# Sensors.net
KiCad netlist of a schematic drawn in Altium Designer
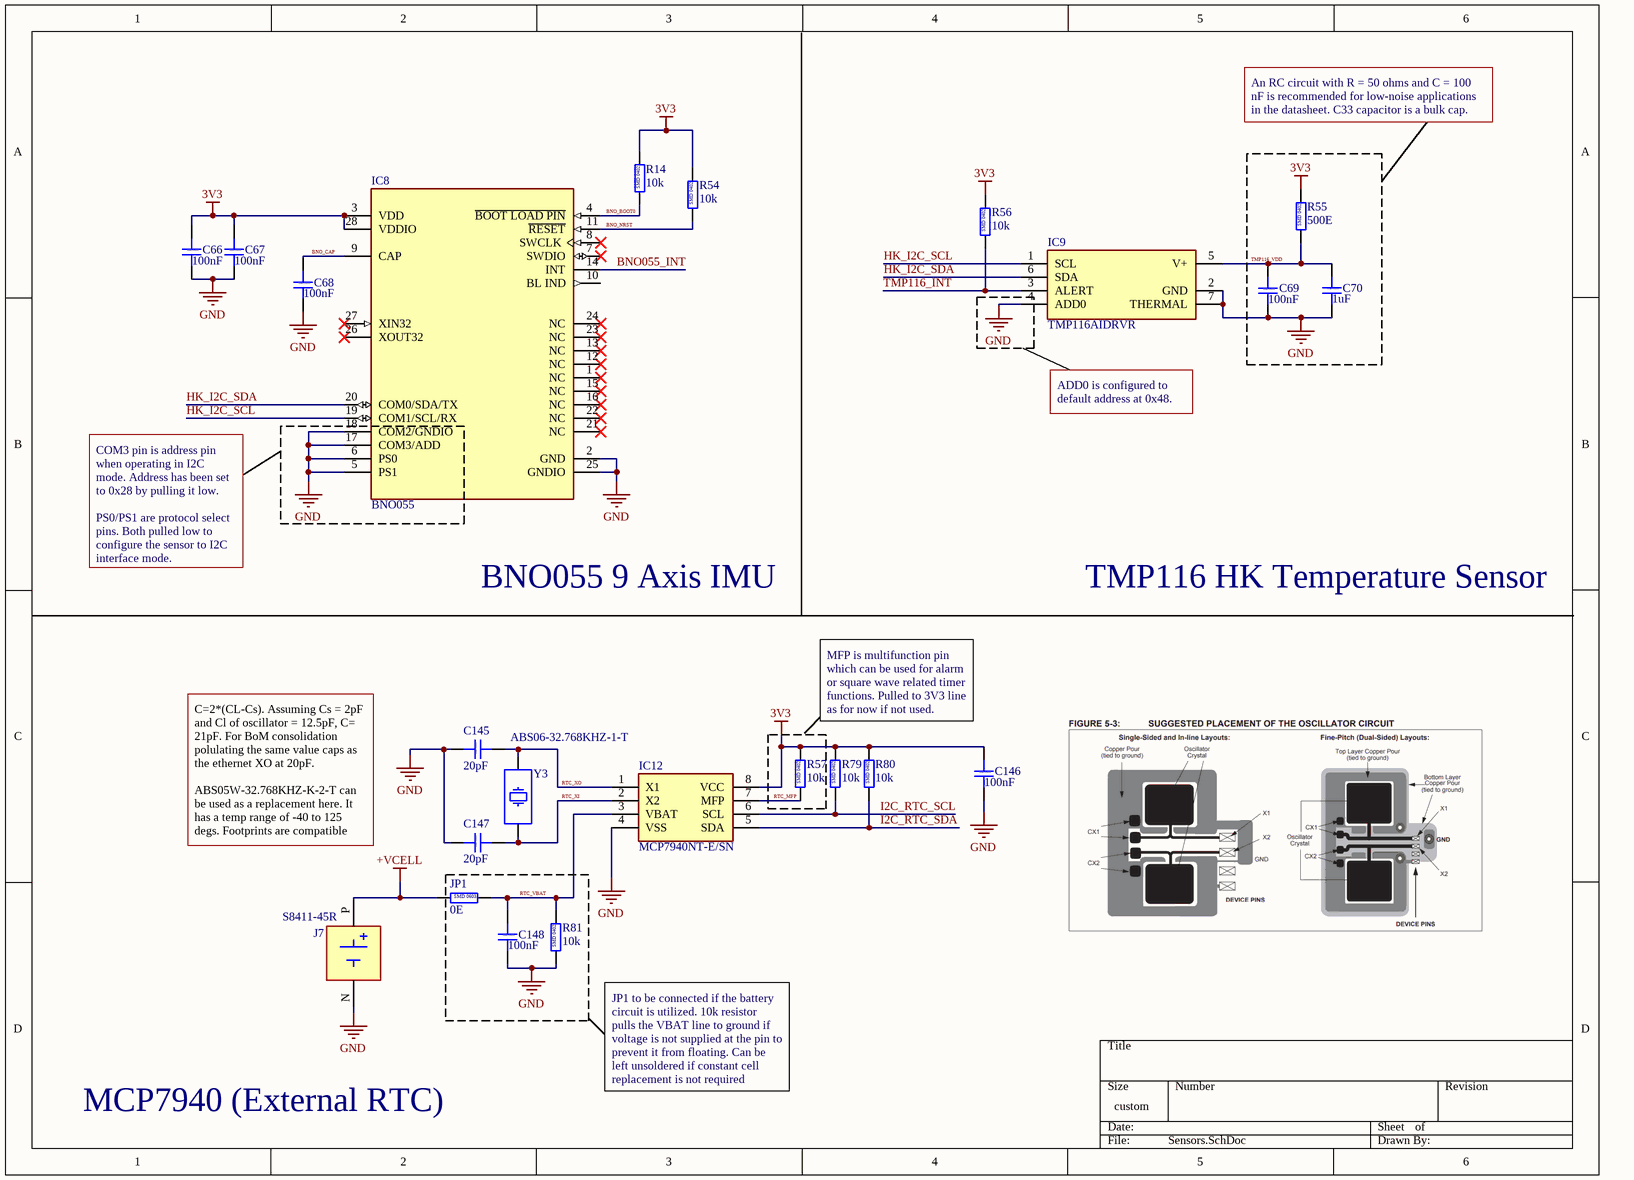
[diagram p0: Sensors.SchDoc]

(export (version "E")
  (design (tool "Eeschema 10.0.6"))
  (components
    (comp (ref "C66")
      (value "100nF")
      (footprint "CAP_0402")
      (description "Capacitor SMD 0402 RATED")
      (libsource (lib "STeRG-Passives-Standard") (part "Capacitor-SMD-0402"))
    )
    (comp (ref "C67")
      (value "100nF")
      (footprint "CAP_0402")
      (description "Capacitor SMD 0402 RATED")
      (libsource (lib "STeRG-Passives-Standard") (part "Capacitor-SMD-0402"))
    )
    (comp (ref "C68")
      (value "100nF")
      (footprint "CAP_0402")
      (description "Capacitor SMD 0402 RATED")
      (libsource (lib "STeRG-Passives-Standard") (part "Capacitor-SMD-0402"))
    )
    (comp (ref "C69")
      (value "100nF")
      (footprint "CAP_0402")
      (description "Capacitor SMD 0402 RATED")
      (libsource (lib "STeRG-Passives-Standard") (part "Capacitor-SMD-0402"))
    )
    (comp (ref "C70")
      (value "1uF")
      (footprint "CAP_0402")
      (description "Capacitor SMD 0402 RATED")
      (libsource (lib "STeRG-Passives-Standard") (part "Capacitor-SMD-0402"))
    )
    (comp (ref "C145")
      (value "20pF")
      (footprint "CAP_0402")
      (description "Capacitor SMD 0402 RATED")
      (libsource (lib "STeRG-Passives-Standard") (part "Capacitor-SMD-0402"))
    )
    (comp (ref "C146")
      (value "100nF")
      (footprint "CAP_0402")
      (description "Capacitor SMD 0402 RATED")
      (libsource (lib "STeRG-Passives-Standard") (part "Capacitor-SMD-0402"))
    )
    (comp (ref "C147")
      (value "20pF")
      (footprint "CAP_0402")
      (description "Capacitor SMD 0402 RATED")
      (libsource (lib "STeRG-Passives-Standard") (part "Capacitor-SMD-0402"))
    )
    (comp (ref "C148")
      (value "100nF")
      (footprint "CAP_0402")
      (description "Capacitor SMD 0402 RATED")
      (libsource (lib "STeRG-Passives-Standard") (part "Capacitor-SMD-0402"))
    )
    (comp (ref "IC8")
      (value "BNO055")
      (footprint "BNO0XX")
      (libsource (lib "STeRG-ICs-Standard") (part "BNO055"))
    )
    (comp (ref "IC9")
      (value "TMP116AIDRVR")
      (footprint "SON65P200X200X80-7N")
      (description "Integrated Circuit")
      (fields (field (name "MOUSER PART NUMBER") "595-TMP116AIDRVR"))
      (libsource (lib "STeRG-ICs-Standard") (part "TMP116AIDRVR"))
    )
    (comp (ref "IC12")
      (value "MCP7940NT-E/SN")
      (footprint "SamacSys:SOIC127P600X175-8N")
      (description "Integrated Circuit")
      (fields
        (field (name "MANUFACTURER_PART_NUMBER") "MCP7940NT-I/SN")
        (field (name "MOUSER PART NUMBER") "579-MCP7940NT-I/SN")
      )
      (libsource (lib "*") (part "MCP7940NT-I_SN"))
    )
    (comp (ref "J7")
      (value "S8411-45R")
      (footprint "HARWIN_S8411-45R")
      (description "Coin Cell Battery Retainer, Horizontal SMT, for CR1220 Coin Cell Batteries, Tape & Reeled")
      (fields (field (name "MF") "Harwin"))
      (libsource (lib "STeRG-Passives-Standard") (part "S8411-45R"))
    )
    (comp (ref "JP1")
      (value "0E")
      (footprint "RES_0603")
      (description "Resistor SMD 0603 RATED")
      (libsource (lib "STeRG-Passives-Standard") (part "Resistor-SMD-0603"))
    )
    (comp (ref "R14")
      (value "10k")
      (footprint "RES_0402")
      (description "Resistor SMD 0402 RATED")
      (libsource (lib "STeRG-Passives-Standard") (part "Resistor-SMD-0402"))
    )
    (comp (ref "R54")
      (value "10k")
      (footprint "RES_0402")
      (description "Resistor SMD 0402 RATED")
      (libsource (lib "STeRG-Passives-Standard") (part "Resistor-SMD-0402"))
    )
    (comp (ref "R55")
      (value "500E")
      (footprint "RES_0402")
      (description "Resistor SMD 0402 RATED")
      (libsource (lib "STeRG-Passives-Standard") (part "Resistor-SMD-0402"))
    )
    (comp (ref "R56")
      (value "10k")
      (footprint "RES_0402")
      (description "Resistor SMD 0402 RATED")
      (libsource (lib "STeRG-Passives-Standard") (part "Resistor-SMD-0402"))
    )
    (comp (ref "R57")
      (value "10k")
      (footprint "RES_0402")
      (description "Resistor SMD 0402 RATED")
      (libsource (lib "STeRG-Passives-Standard") (part "Resistor-SMD-0402"))
    )
    (comp (ref "R79")
      (value "10k")
      (footprint "RES_0402")
      (description "Resistor SMD 0402 RATED")
      (libsource (lib "STeRG-Passives-Standard") (part "Resistor-SMD-0402"))
    )
    (comp (ref "R80")
      (value "10k")
      (footprint "RES_0402")
      (description "Resistor SMD 0402 RATED")
      (libsource (lib "STeRG-Passives-Standard") (part "Resistor-SMD-0402"))
    )
    (comp (ref "R81")
      (value "10k")
      (footprint "RES_0402")
      (description "Resistor SMD 0402 RATED")
      (libsource (lib "STeRG-Passives-Standard") (part "Resistor-SMD-0402"))
    )
    (comp (ref "Y3")
      (value "ABS06-32.768KHZ-1-T")
      (footprint "SamacSys:ABS06")
      (description "Crystal or Oscillator")
      (fields (field (name "MOUSER PART NUMBER") "815-ABS06-32.7K-1-T"))
      (libsource (lib "STeRG-Passives-Standard") (part "ABS06-32.768KHZ-1-T"))
    )
  )
  (nets
    (net (code "1") (name "+VCELL") (class "Default")
      (node (ref "J7") (pin "P") (pinfunction "POS_P") (pintype "passive"))
      (node (ref "JP1") (pin "1") (pinfunction "1_1") (pintype "passive"))
    )
    (net (code "2") (name "/BNO055_INT") (class "Default")
      (node (ref "IC8") (pin "14") (pinfunction "INT_14") (pintype "passive"))
    )
    (net (code "3") (name "/BNO_BOOT0") (class "Default")
      (node (ref "IC8") (pin "4") (pinfunction "~{BOOT_LOAD_PIN}_4") (pintype "input"))
      (node (ref "R14") (pin "1") (pinfunction "1_1") (pintype "passive"))
    )
    (net (code "4") (name "/BNO_CAP") (class "Default")
      (node (ref "C68") (pin "1") (pinfunction "1_1") (pintype "passive"))
      (node (ref "IC8") (pin "9") (pinfunction "CAP_9") (pintype "passive"))
    )
    (net (code "5") (name "/BNO_NRST") (class "Default")
      (node (ref "IC8") (pin "11") (pinfunction "~{RESET}_11") (pintype "input"))
      (node (ref "R54") (pin "1") (pinfunction "1_1") (pintype "passive"))
    )
    (net (code "6") (name "/HK_I2C_SCL") (class "Default")
      (node (ref "IC8") (pin "19") (pinfunction "COM1/SCL/RX_19") (pintype "bidirectional"))
      (node (ref "IC9") (pin "1") (pinfunction "SCL_1") (pintype "passive"))
    )
    (net (code "7") (name "/HK_I2C_SDA") (class "Default")
      (node (ref "IC8") (pin "20") (pinfunction "COM0/SDA/TX_20") (pintype "bidirectional"))
      (node (ref "IC9") (pin "6") (pinfunction "SDA_6") (pintype "passive"))
    )
    (net (code "8") (name "/I2C_RTC_SCL") (class "Default")
      (node (ref "IC12") (pin "6") (pinfunction "SCL_6") (pintype "passive"))
      (node (ref "R79") (pin "1") (pinfunction "1_1") (pintype "passive"))
    )
    (net (code "9") (name "/I2C_RTC_SDA") (class "Default")
      (node (ref "IC12") (pin "5") (pinfunction "SDA_5") (pintype "passive"))
      (node (ref "R80") (pin "1") (pinfunction "1_1") (pintype "passive"))
    )
    (net (code "10") (name "/RTC_MFP") (class "Default")
      (node (ref "IC12") (pin "7") (pinfunction "MFP_7") (pintype "passive"))
      (node (ref "R57") (pin "1") (pinfunction "1_1") (pintype "passive"))
    )
    (net (code "11") (name "/RTC_VBAT") (class "Default")
      (node (ref "C148") (pin "1") (pinfunction "1_1") (pintype "passive"))
      (node (ref "IC12") (pin "3") (pinfunction "VBAT_3") (pintype "passive"))
      (node (ref "JP1") (pin "2") (pinfunction "2_2") (pintype "passive"))
      (node (ref "R81") (pin "2") (pinfunction "2_2") (pintype "passive"))
    )
    (net (code "12") (name "/RTC_XI") (class "Default")
      (node (ref "C147") (pin "2") (pinfunction "2_2") (pintype "passive"))
      (node (ref "IC12") (pin "2") (pinfunction "X2_2") (pintype "passive"))
      (node (ref "Y3") (pin "1") (pinfunction "1_1") (pintype "passive"))
    )
    (net (code "13") (name "/RTC_XO") (class "Default")
      (node (ref "C145") (pin "2") (pinfunction "2_2") (pintype "passive"))
      (node (ref "IC12") (pin "1") (pinfunction "X1_1") (pintype "passive"))
      (node (ref "Y3") (pin "2") (pinfunction "2_2") (pintype "passive"))
    )
    (net (code "14") (name "/TMP116_INT") (class "Default")
      (node (ref "IC9") (pin "3") (pinfunction "ALERT_3") (pintype "passive"))
      (node (ref "R56") (pin "1") (pinfunction "1_1") (pintype "passive"))
    )
    (net (code "15") (name "/TMP116_VDD") (class "Default")
      (node (ref "C69") (pin "1") (pinfunction "1_1") (pintype "passive"))
      (node (ref "C70") (pin "1") (pinfunction "1_1") (pintype "passive"))
      (node (ref "IC9") (pin "5") (pinfunction "V+_5") (pintype "passive"))
      (node (ref "R55") (pin "1") (pinfunction "1_1") (pintype "passive"))
    )
    (net (code "16") (name "3V3") (class "Default")
      (node (ref "C146") (pin "1") (pinfunction "1_1") (pintype "passive"))
      (node (ref "C66") (pin "1") (pinfunction "1_1") (pintype "passive"))
      (node (ref "C67") (pin "1") (pinfunction "1_1") (pintype "passive"))
      (node (ref "IC12") (pin "8") (pinfunction "VCC_8") (pintype "passive"))
      (node (ref "IC8") (pin "28") (pinfunction "VDDIO_28") (pintype "power_in"))
      (node (ref "IC8") (pin "3") (pinfunction "VDD_3") (pintype "power_in"))
      (node (ref "R14") (pin "2") (pinfunction "2_2") (pintype "passive"))
      (node (ref "R54") (pin "2") (pinfunction "2_2") (pintype "passive"))
      (node (ref "R55") (pin "2") (pinfunction "2_2") (pintype "passive"))
      (node (ref "R56") (pin "2") (pinfunction "2_2") (pintype "passive"))
      (node (ref "R57") (pin "2") (pinfunction "2_2") (pintype "passive"))
      (node (ref "R79") (pin "2") (pinfunction "2_2") (pintype "passive"))
      (node (ref "R80") (pin "2") (pinfunction "2_2") (pintype "passive"))
    )
    (net (code "17") (name "GND") (class "Default")
      (node (ref "C145") (pin "1") (pinfunction "1_1") (pintype "passive"))
      (node (ref "C146") (pin "2") (pinfunction "2_2") (pintype "passive"))
      (node (ref "C147") (pin "1") (pinfunction "1_1") (pintype "passive"))
      (node (ref "C148") (pin "2") (pinfunction "2_2") (pintype "passive"))
      (node (ref "C66") (pin "2") (pinfunction "2_2") (pintype "passive"))
      (node (ref "C67") (pin "2") (pinfunction "2_2") (pintype "passive"))
      (node (ref "C68") (pin "2") (pinfunction "2_2") (pintype "passive"))
      (node (ref "C69") (pin "2") (pinfunction "2_2") (pintype "passive"))
      (node (ref "C70") (pin "2") (pinfunction "2_2") (pintype "passive"))
      (node (ref "IC12") (pin "4") (pinfunction "VSS_4") (pintype "passive"))
      (node (ref "IC8") (pin "17") (pinfunction "COM3/ADD_17") (pintype "passive"))
      (node (ref "IC8") (pin "18") (pinfunction "COM2/GNDIO_18") (pintype "passive"))
      (node (ref "IC8") (pin "2") (pinfunction "GND_2") (pintype "passive"))
      (node (ref "IC8") (pin "25") (pinfunction "GNDIO_25") (pintype "passive"))
      (node (ref "IC8") (pin "5") (pinfunction "PS1_5") (pintype "passive"))
      (node (ref "IC8") (pin "6") (pinfunction "PS0_6") (pintype "passive"))
      (node (ref "IC9") (pin "2") (pinfunction "GND_2") (pintype "passive"))
      (node (ref "IC9") (pin "4") (pinfunction "ADD0_4") (pintype "passive"))
      (node (ref "IC9") (pin "7") (pinfunction "THERMAL_7") (pintype "passive"))
      (node (ref "J7") (pin "N") (pinfunction "NEG_N") (pintype "passive"))
      (node (ref "R81") (pin "1") (pinfunction "1_1") (pintype "passive"))
    )
    (net (code "18") (name "unconnected-(IC8-BL_IND-Pad10)") (class "Default")
      (node (ref "IC8") (pin "10") (pinfunction "BL_IND_10") (pintype "output"))
    )
    (net (code "19") (name "unconnected-(IC8-NC-Pad1)") (class "Default")
      (node (ref "IC8") (pin "1") (pinfunction "NC_1") (pintype "passive+no_connect"))
    )
    (net (code "20") (name "unconnected-(IC8-NC-Pad12)") (class "Default")
      (node (ref "IC8") (pin "12") (pinfunction "NC_12") (pintype "passive+no_connect"))
    )
    (net (code "21") (name "unconnected-(IC8-NC-Pad13)") (class "Default")
      (node (ref "IC8") (pin "13") (pinfunction "NC_13") (pintype "passive+no_connect"))
    )
    (net (code "22") (name "unconnected-(IC8-NC-Pad15)") (class "Default")
      (node (ref "IC8") (pin "15") (pinfunction "NC_15") (pintype "passive+no_connect"))
    )
    (net (code "23") (name "unconnected-(IC8-NC-Pad16)") (class "Default")
      (node (ref "IC8") (pin "16") (pinfunction "NC_16") (pintype "passive+no_connect"))
    )
    (net (code "24") (name "unconnected-(IC8-NC-Pad21)") (class "Default")
      (node (ref "IC8") (pin "21") (pinfunction "NC_21") (pintype "passive+no_connect"))
    )
    (net (code "25") (name "unconnected-(IC8-NC-Pad22)") (class "Default")
      (node (ref "IC8") (pin "22") (pinfunction "NC_22") (pintype "passive+no_connect"))
    )
    (net (code "26") (name "unconnected-(IC8-NC-Pad23)") (class "Default")
      (node (ref "IC8") (pin "23") (pinfunction "NC_23") (pintype "passive+no_connect"))
    )
    (net (code "27") (name "unconnected-(IC8-NC-Pad24)") (class "Default")
      (node (ref "IC8") (pin "24") (pinfunction "NC_24") (pintype "passive+no_connect"))
    )
    (net (code "28") (name "unconnected-(IC8-SWCLK-Pad8)") (class "Default")
      (node (ref "IC8") (pin "8") (pinfunction "SWCLK_8") (pintype "input+no_connect"))
    )
    (net (code "29") (name "unconnected-(IC8-SWDIO-Pad7)") (class "Default")
      (node (ref "IC8") (pin "7") (pinfunction "SWDIO_7") (pintype "bidirectional+no_connect"))
    )
    (net (code "30") (name "unconnected-(IC8-XIN32-Pad27)") (class "Default")
      (node (ref "IC8") (pin "27") (pinfunction "XIN32_27") (pintype "input+no_connect"))
    )
    (net (code "31") (name "unconnected-(IC8-XOUT32-Pad26)") (class "Default")
      (node (ref "IC8") (pin "26") (pinfunction "XOUT32_26") (pintype "passive+no_connect"))
    )
  )
)
